# LPmini-Prototype_1_3_bga.net
KiCad netlist of a schematic drawn in EAGLE
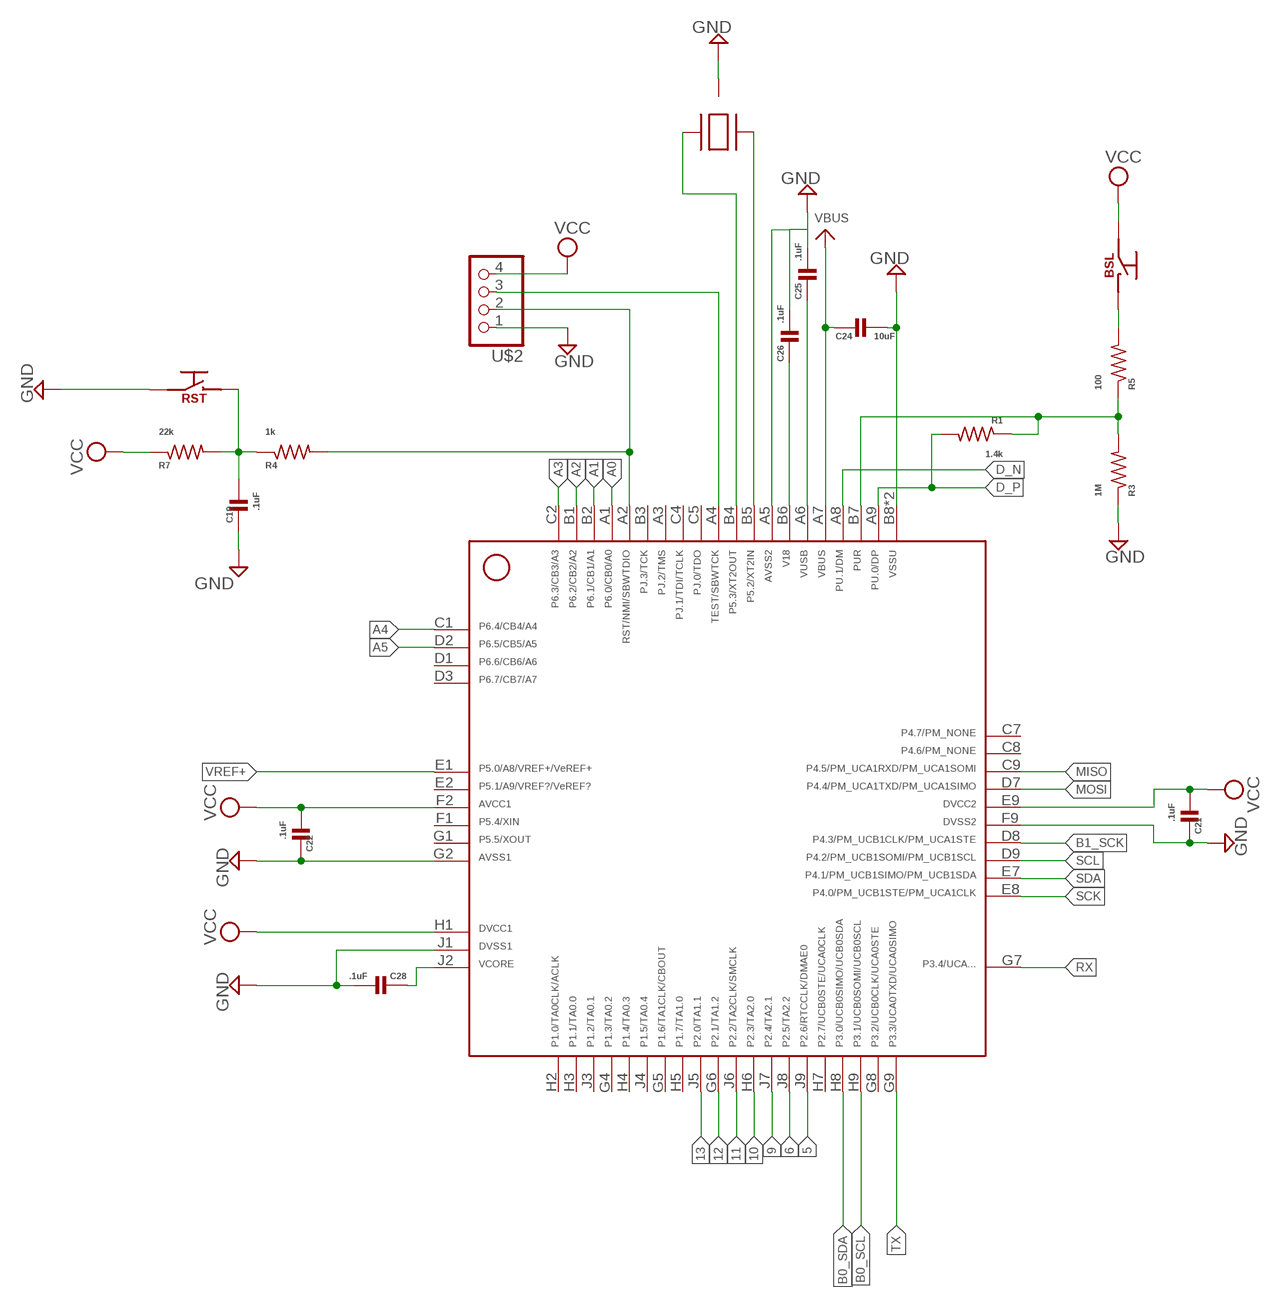
[diagram p0: schematic, sheet 1, part 1 of 2]
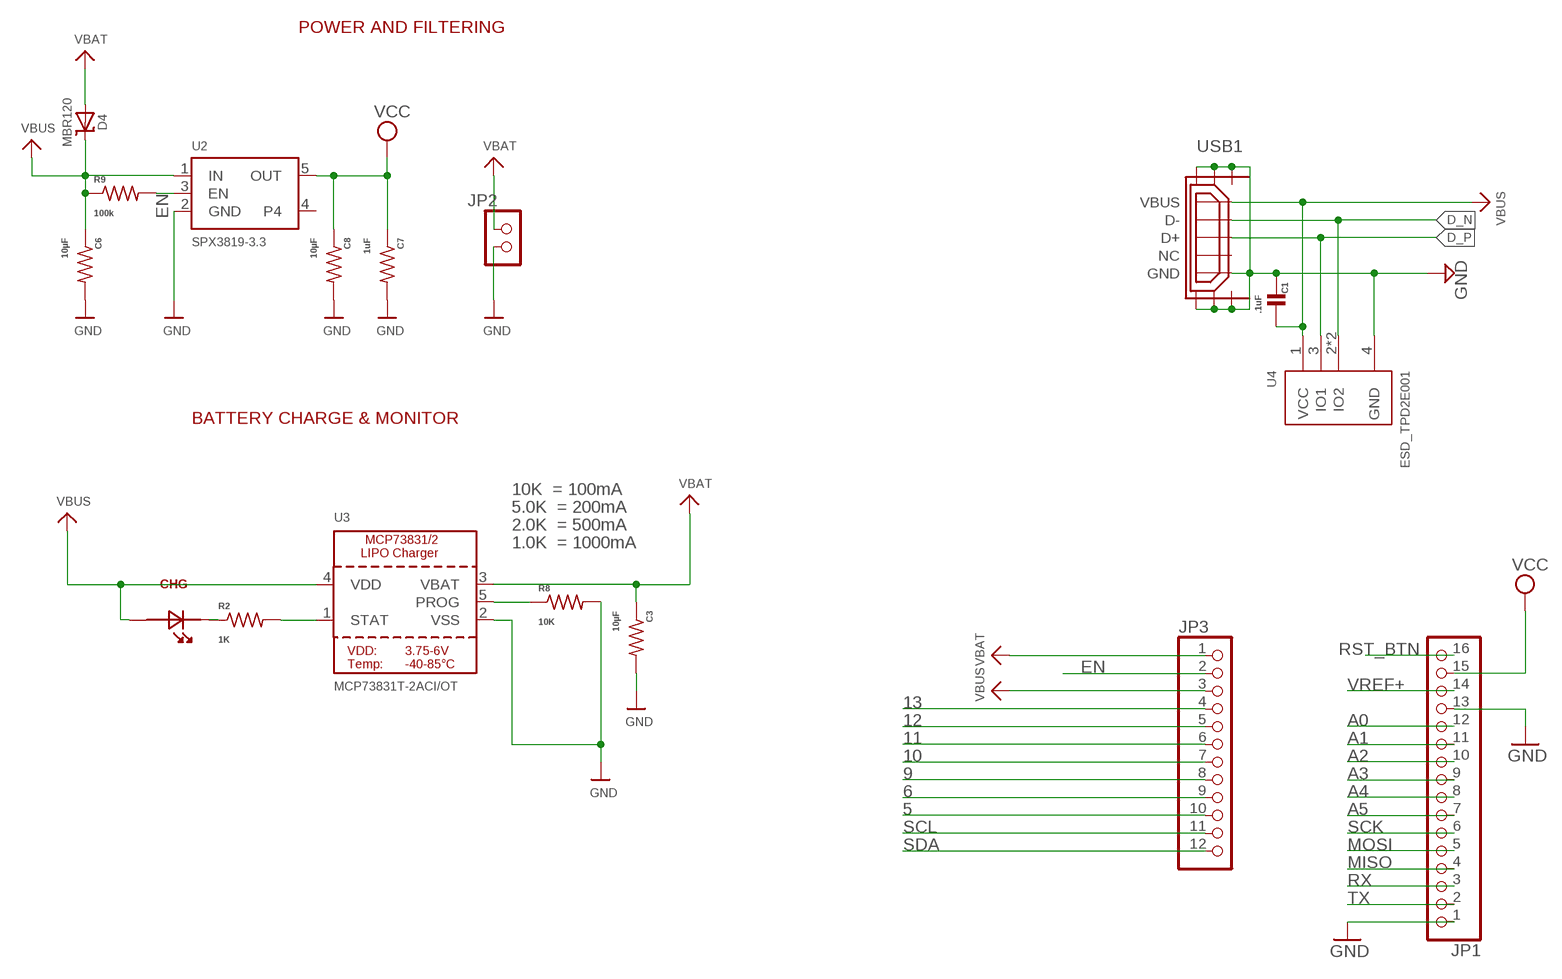
[diagram p1: schematic, sheet 1, part 2 of 2]

(export (version "E")
  (design (tool "Eeschema 10.0.6"))
  (components
    (comp (ref "BSL")
      (value "PB_SMALL_SMD")
      (footprint "eagle-import:PB_KMR2")
      (libsource (lib "eagle-import") (part "PB_SMALL_SMD"))
    )
    (comp (ref "C1")
      (value ".1uF")
      (footprint "eagle-import:C0402")
      (libsource (lib "eagle-import") (part "C-EUC0402"))
    )
    (comp (ref "C3")
      (value "10µF")
      (footprint "eagle-import:R0603")
      (libsource (lib "eagle-import") (part "R-US_R0603"))
    )
    (comp (ref "C6")
      (value "10µF")
      (footprint "eagle-import:R0603")
      (libsource (lib "eagle-import") (part "R-US_R0603"))
    )
    (comp (ref "C7")
      (value "1uF")
      (footprint "eagle-import:R0402")
      (libsource (lib "eagle-import") (part "R-US_R0402"))
    )
    (comp (ref "C8")
      (value "10µF")
      (footprint "eagle-import:R0603")
      (libsource (lib "eagle-import") (part "R-US_R0603"))
    )
    (comp (ref "C19")
      (value ".1uF")
      (footprint "eagle-import:C0402")
      (libsource (lib "eagle-import") (part "C-EUC0402"))
    )
    (comp (ref "C21")
      (value ".1uF")
      (footprint "eagle-import:C0402")
      (libsource (lib "eagle-import") (part "C-EUC0402"))
    )
    (comp (ref "C22")
      (value ".1uF")
      (footprint "eagle-import:C0402")
      (libsource (lib "eagle-import") (part "C-EUC0402"))
    )
    (comp (ref "C24")
      (value "10uF")
      (footprint "eagle-import:C0603")
      (libsource (lib "eagle-import") (part "C-EUC0603"))
    )
    (comp (ref "C25")
      (value ".1uF")
      (footprint "eagle-import:C0402")
      (libsource (lib "eagle-import") (part "C-EUC0402"))
    )
    (comp (ref "C26")
      (value ".1uF")
      (footprint "eagle-import:C0402")
      (libsource (lib "eagle-import") (part "C-EUC0402"))
    )
    (comp (ref "C28")
      (value ".1uF")
      (footprint "eagle-import:C0402")
      (libsource (lib "eagle-import") (part "C-EUC0402"))
    )
    (comp (ref "CHG")
      (value "ORANGE")
      (footprint "eagle-import:LED_0603")
      (libsource (lib "eagle-import") (part "LED0603"))
    )
    (comp (ref "D4")
      (value "MBR120")
      (footprint "eagle-import:SOD-123")
      (libsource (lib "eagle-import") (part "DIODE-SCHOTTKYSOD-123"))
    )
    (comp (ref "JP1")
      (value "HEADER-1X16ROUND")
      (footprint "eagle-import:1X16_ROUND")
      (libsource (lib "eagle-import") (part "HEADER-1X16ROUND"))
    )
    (comp (ref "JP2")
      (value "0_JOSEPH_PINHD-1X2END")
      (footprint "eagle-import:0_JOSEPH_1X02-END")
      (libsource (lib "eagle-import") (part "0_JOSEPH_PINHD-1X2END"))
    )
    (comp (ref "JP3")
      (value "HEADER-1X12")
      (footprint "eagle-import:1X12_ROUND")
      (libsource (lib "eagle-import") (part "HEADER-1X12"))
    )
    (comp (ref "R1")
      (value "1.4k")
      (footprint "eagle-import:R0402")
      (libsource (lib "eagle-import") (part "R-US_R0402"))
    )
    (comp (ref "R2")
      (value "1K")
      (footprint "eagle-import:R0402")
      (libsource (lib "eagle-import") (part "R-US_R0402"))
    )
    (comp (ref "R3")
      (value "1M")
      (footprint "eagle-import:R0402")
      (libsource (lib "eagle-import") (part "R-US_R0402"))
    )
    (comp (ref "R4")
      (value "1k")
      (footprint "eagle-import:R0402")
      (libsource (lib "eagle-import") (part "R-US_R0402"))
    )
    (comp (ref "R5")
      (value "100")
      (footprint "eagle-import:R0402")
      (libsource (lib "eagle-import") (part "R-US_R0402"))
    )
    (comp (ref "R7")
      (value "22k")
      (footprint "eagle-import:R0402")
      (libsource (lib "eagle-import") (part "R-US_R0402"))
    )
    (comp (ref "R8")
      (value "10K")
      (footprint "eagle-import:R0402")
      (libsource (lib "eagle-import") (part "R-US_R0402"))
    )
    (comp (ref "R9")
      (value "100k")
      (footprint "eagle-import:R0402")
      (libsource (lib "eagle-import") (part "R-US_R0402"))
    )
    (comp (ref "RST")
      (value "PB_SMALL_SMD")
      (footprint "eagle-import:PB_KMR2")
      (libsource (lib "eagle-import") (part "PB_SMALL_SMD"))
    )
    (comp (ref "U$2")
      (value "PINHD_1X4MOLEX_4_1MM")
      (footprint "eagle-import:MOLEX_4_1MM")
      (libsource (lib "eagle-import") (part "PINHD_1X4MOLEX_4_1MM"))
    )
    (comp (ref "U$4")
      (value "MSP430F5528")
      (footprint "eagle-import:80_BGA_MICROSTAR")
      (libsource (lib "eagle-import") (part "MSP430F5528"))
    )
    (comp (ref "U$5")
      (value "CRYSTAL_SMD")
      (footprint "eagle-import:SMD_CRYSTAL")
      (libsource (lib "eagle-import") (part "CRYSTAL_SMD"))
    )
    (comp (ref "U2")
      (value "SPX3819-3.3")
      (footprint "eagle-import:SOT23-5")
      (libsource (lib "eagle-import") (part "VREG_SOT23-5"))
    )
    (comp (ref "U3")
      (value "MCP73831T-2ACI/OT")
      (footprint "eagle-import:SOT23-5")
      (libsource (lib "eagle-import") (part "MCP73831/2"))
    )
    (comp (ref "U4")
      (value "ESD_TPD2E001")
      (footprint "eagle-import:PROJECT7264_TPD2E001-DRL")
      (libsource (lib "eagle-import") (part "ESD_TPD2E001"))
    )
    (comp (ref "USB1")
      (value "USB_CON-UPDATE_USB_MICRO_FLIPPED")
      (footprint "eagle-import:USB_CON-UPDATE_HIROSE-ZX62R-B-5P")
      (libsource (lib "eagle-import") (part "USB_CON-UPDATE_USB_MICRO_FLIPPED"))
    )
  )
  (nets
    (net (code "1") (name "/EN") (class "Default")
      (node (ref "JP3") (pin "2") (pinfunction "2_2") (pintype "passive"))
      (node (ref "R9") (pin "2") (pinfunction "2_2") (pintype "passive"))
      (node (ref "U2") (pin "3") (pinfunction "EN_3") (pintype "input"))
    )
    (net (code "2") (name "/RST_BTN") (class "Default")
      (node (ref "C19") (pin "1") (pinfunction "1_1") (pintype "passive"))
      (node (ref "JP1") (pin "16") (pinfunction "16_16") (pintype "passive"))
      (node (ref "R4") (pin "1") (pinfunction "1_1") (pintype "passive"))
      (node (ref "R7") (pin "2") (pinfunction "2_2") (pintype "passive"))
      (node (ref "RST") (pin "2A") (pinfunction "B_2A") (pintype "bidirectional"))
      (node (ref "RST") (pin "2B") (pinfunction "B_2B") (pintype "bidirectional"))
    )
    (net (code "3") (name "5") (class "Default")
      (node (ref "JP3") (pin "10") (pinfunction "10_10") (pintype "passive"))
      (node (ref "U$4") (pin "J9") (pinfunction "J9_J9") (pintype "bidirectional"))
    )
    (net (code "4") (name "6") (class "Default")
      (node (ref "JP3") (pin "9") (pinfunction "9_9") (pintype "passive"))
      (node (ref "U$4") (pin "J8") (pinfunction "J8_J8") (pintype "bidirectional"))
    )
    (net (code "5") (name "9") (class "Default")
      (node (ref "JP3") (pin "8") (pinfunction "8_8") (pintype "passive"))
      (node (ref "U$4") (pin "J7") (pinfunction "J7_J7") (pintype "bidirectional"))
    )
    (net (code "6") (name "10") (class "Default")
      (node (ref "JP3") (pin "7") (pinfunction "7_7") (pintype "passive"))
      (node (ref "U$4") (pin "H6") (pinfunction "H6_H6") (pintype "bidirectional"))
    )
    (net (code "7") (name "11") (class "Default")
      (node (ref "JP3") (pin "6") (pinfunction "6_6") (pintype "passive"))
      (node (ref "U$4") (pin "J6") (pinfunction "J6_J6") (pintype "bidirectional"))
    )
    (net (code "8") (name "12") (class "Default")
      (node (ref "JP3") (pin "5") (pinfunction "5_5") (pintype "passive"))
      (node (ref "U$4") (pin "G6") (pinfunction "G6_G6") (pintype "bidirectional"))
    )
    (net (code "9") (name "13") (class "Default")
      (node (ref "JP3") (pin "4") (pinfunction "4_4") (pintype "passive"))
      (node (ref "U$4") (pin "J5") (pinfunction "J5_J5") (pintype "bidirectional"))
    )
    (net (code "10") (name "A0") (class "Default")
      (node (ref "JP1") (pin "12") (pinfunction "12_12") (pintype "passive"))
      (node (ref "U$4") (pin "A1") (pinfunction "A1_A1") (pintype "bidirectional"))
    )
    (net (code "11") (name "A1") (class "Default")
      (node (ref "JP1") (pin "11") (pinfunction "11_11") (pintype "passive"))
      (node (ref "U$4") (pin "B2") (pinfunction "B2_B2") (pintype "bidirectional"))
    )
    (net (code "12") (name "A2") (class "Default")
      (node (ref "JP1") (pin "10") (pinfunction "10_10") (pintype "passive"))
      (node (ref "U$4") (pin "B1") (pinfunction "B1_B1") (pintype "bidirectional"))
    )
    (net (code "13") (name "A3") (class "Default")
      (node (ref "JP1") (pin "9") (pinfunction "9_9") (pintype "passive"))
      (node (ref "U$4") (pin "C2") (pinfunction "C2_C2") (pintype "bidirectional"))
    )
    (net (code "14") (name "A4") (class "Default")
      (node (ref "JP1") (pin "8") (pinfunction "8_8") (pintype "passive"))
      (node (ref "U$4") (pin "C1") (pinfunction "C1_C1") (pintype "bidirectional"))
    )
    (net (code "15") (name "A5") (class "Default")
      (node (ref "JP1") (pin "7") (pinfunction "7_7") (pintype "passive"))
      (node (ref "U$4") (pin "D2") (pinfunction "D2_D2") (pintype "bidirectional"))
    )
    (net (code "16") (name "B0_SCL") (class "Default")
      (node (ref "U$4") (pin "H9") (pinfunction "H9_H9") (pintype "bidirectional"))
    )
    (net (code "17") (name "B0_SDA") (class "Default")
      (node (ref "U$4") (pin "H8") (pinfunction "H8_H8") (pintype "bidirectional"))
    )
    (net (code "18") (name "B1_SCK") (class "Default")
      (node (ref "U$4") (pin "D8") (pinfunction "D8_D8") (pintype "bidirectional"))
    )
    (net (code "19") (name "D_N") (class "Default")
      (node (ref "U$4") (pin "A8") (pinfunction "A8_A8") (pintype "bidirectional"))
      (node (ref "U4") (pin "2") (pinfunction "IO2_2") (pintype "bidirectional"))
      (node (ref "U4") (pin "5") (pinfunction "IO2_5") (pintype "bidirectional"))
      (node (ref "USB1") (pin "D-") (pinfunction "D-_D-") (pintype "input"))
    )
    (net (code "20") (name "D_P") (class "Default")
      (node (ref "R1") (pin "2") (pinfunction "2_2") (pintype "passive"))
      (node (ref "U$4") (pin "A9") (pinfunction "A9_A9") (pintype "bidirectional"))
      (node (ref "U4") (pin "3") (pinfunction "IO1_3") (pintype "bidirectional"))
      (node (ref "USB1") (pin "D+") (pinfunction "D+_D+") (pintype "input"))
    )
    (net (code "21") (name "GND") (class "Default")
      (node (ref "C1") (pin "2") (pinfunction "2_2") (pintype "passive"))
      (node (ref "C19") (pin "2") (pinfunction "2_2") (pintype "passive"))
      (node (ref "C21") (pin "2") (pinfunction "2_2") (pintype "passive"))
      (node (ref "C22") (pin "2") (pinfunction "2_2") (pintype "passive"))
      (node (ref "C24") (pin "2") (pinfunction "2_2") (pintype "passive"))
      (node (ref "C25") (pin "2") (pinfunction "2_2") (pintype "passive"))
      (node (ref "C26") (pin "2") (pinfunction "2_2") (pintype "passive"))
      (node (ref "C28") (pin "2") (pinfunction "2_2") (pintype "passive"))
      (node (ref "C3") (pin "2") (pinfunction "2_2") (pintype "passive"))
      (node (ref "C6") (pin "2") (pinfunction "2_2") (pintype "passive"))
      (node (ref "C7") (pin "2") (pinfunction "2_2") (pintype "passive"))
      (node (ref "C8") (pin "2") (pinfunction "2_2") (pintype "passive"))
      (node (ref "JP1") (pin "1") (pinfunction "1_1") (pintype "passive"))
      (node (ref "JP1") (pin "13") (pinfunction "13_13") (pintype "passive"))
      (node (ref "JP2") (pin "2") (pinfunction "2_2") (pintype "passive"))
      (node (ref "R3") (pin "1") (pinfunction "1_1") (pintype "passive"))
      (node (ref "R8") (pin "2") (pinfunction "2_2") (pintype "passive"))
      (node (ref "RST") (pin "1A") (pinfunction "A_1A") (pintype "bidirectional"))
      (node (ref "RST") (pin "1B") (pinfunction "A_1B") (pintype "bidirectional"))
      (node (ref "U$2") (pin "1") (pinfunction "1_1") (pintype "passive"))
      (node (ref "U$4") (pin "A5") (pinfunction "A5_A5") (pintype "power_in"))
      (node (ref "U$4") (pin "B8") (pinfunction "B8,B9_B8") (pintype "power_in"))
      (node (ref "U$4") (pin "B9") (pinfunction "B8,B9_B9") (pintype "power_in"))
      (node (ref "U$4") (pin "F9") (pinfunction "F9_F9") (pintype "power_in"))
      (node (ref "U$4") (pin "G2") (pinfunction "G2_G2") (pintype "power_in"))
      (node (ref "U$4") (pin "J1") (pinfunction "J1_J1") (pintype "power_in"))
      (node (ref "U$5") (pin "2") (pinfunction "GND_2") (pintype "bidirectional"))
      (node (ref "U$5") (pin "4") (pinfunction "GND_4") (pintype "bidirectional"))
      (node (ref "U2") (pin "2") (pinfunction "GND_2") (pintype "power_in"))
      (node (ref "U3") (pin "2") (pinfunction "VSS_2") (pintype "power_in"))
      (node (ref "U4") (pin "4") (pinfunction "GND_4") (pintype "power_in"))
      (node (ref "USB1") (pin "GND") (pinfunction "GND_GND") (pintype "input"))
      (node (ref "USB1") (pin "SHIELD1") (pinfunction "SHIELD1_SHIELD1") (pintype "bidirectional"))
      (node (ref "USB1") (pin "SHIELD2") (pinfunction "SHIELD2_SHIELD2") (pintype "bidirectional"))
      (node (ref "USB1") (pin "SHIELD3") (pinfunction "SHIELD3_SHIELD3") (pintype "bidirectional"))
      (node (ref "USB1") (pin "SHIELD4") (pinfunction "SHIELD4_SHIELD4") (pintype "bidirectional"))
      (node (ref "USB1") (pin "SHIELD5") (pinfunction "SHIELD5_SHIELD5") (pintype "bidirectional"))
      (node (ref "USB1") (pin "SHIELD6") (pinfunction "SHIELD6_SHIELD6") (pintype "bidirectional"))
    )
    (net (code "22") (name "MISO") (class "Default")
      (node (ref "JP1") (pin "4") (pinfunction "4_4") (pintype "passive"))
      (node (ref "U$4") (pin "C9") (pinfunction "C9_C9") (pintype "bidirectional"))
    )
    (net (code "23") (name "MOSI") (class "Default")
      (node (ref "JP1") (pin "5") (pinfunction "5_5") (pintype "passive"))
      (node (ref "U$4") (pin "D7") (pinfunction "D7_D7") (pintype "bidirectional"))
    )
    (net (code "24") (name "Net-(BSL-B-Pad2A)") (class "Default")
      (node (ref "BSL") (pin "2A") (pinfunction "B_2A") (pintype "bidirectional"))
      (node (ref "BSL") (pin "2B") (pinfunction "B_2B") (pintype "bidirectional"))
      (node (ref "R5") (pin "2") (pinfunction "2_2") (pintype "passive"))
    )
    (net (code "25") (name "Net-(C25-Pad1)") (class "Default")
      (node (ref "C25") (pin "1") (pinfunction "1_1") (pintype "passive"))
      (node (ref "U$4") (pin "A6") (pinfunction "A6_A6") (pintype "power_in"))
    )
    (net (code "26") (name "Net-(C26-Pad1)") (class "Default")
      (node (ref "C26") (pin "1") (pinfunction "1_1") (pintype "passive"))
      (node (ref "U$4") (pin "B6") (pinfunction "B6_B6") (pintype "power_in"))
    )
    (net (code "27") (name "Net-(C28-Pad1)") (class "Default")
      (node (ref "C28") (pin "1") (pinfunction "1_1") (pintype "passive"))
      (node (ref "U$4") (pin "J2") (pinfunction "J2_J2") (pintype "power_in"))
    )
    (net (code "28") (name "Net-(CHG-C)") (class "Default")
      (node (ref "CHG") (pin "K") (pinfunction "C_K") (pintype "bidirectional"))
      (node (ref "R2") (pin "1") (pinfunction "1_1") (pintype "passive"))
    )
    (net (code "29") (name "Net-(R1-Pad1)") (class "Default")
      (node (ref "R1") (pin "1") (pinfunction "1_1") (pintype "passive"))
      (node (ref "R3") (pin "2") (pinfunction "2_2") (pintype "passive"))
      (node (ref "R5") (pin "1") (pinfunction "1_1") (pintype "passive"))
      (node (ref "U$4") (pin "B7") (pinfunction "B7_B7") (pintype "bidirectional"))
    )
    (net (code "30") (name "Net-(R4-Pad2)") (class "Default")
      (node (ref "R4") (pin "2") (pinfunction "2_2") (pintype "passive"))
      (node (ref "U$2") (pin "2") (pinfunction "2_2") (pintype "passive"))
      (node (ref "U$4") (pin "A2") (pinfunction "A2_A2") (pintype "bidirectional"))
    )
    (net (code "31") (name "Net-(U$2-Pad3)") (class "Default")
      (node (ref "U$2") (pin "3") (pinfunction "3_3") (pintype "passive"))
      (node (ref "U$4") (pin "A4") (pinfunction "A4_A4") (pintype "input"))
    )
    (net (code "32") (name "Net-(U$5-P$1)") (class "Default")
      (node (ref "U$4") (pin "B5") (pinfunction "B5_B5") (pintype "bidirectional"))
      (node (ref "U$5") (pin "1") (pinfunction "P$1_1") (pintype "bidirectional"))
    )
    (net (code "33") (name "Net-(U$5-P$2)") (class "Default")
      (node (ref "U$4") (pin "B4") (pinfunction "B4_B4") (pintype "bidirectional"))
      (node (ref "U$5") (pin "3") (pinfunction "P$2_3") (pintype "bidirectional"))
    )
    (net (code "34") (name "Net-(U3-PROG)") (class "Default")
      (node (ref "R8") (pin "1") (pinfunction "1_1") (pintype "passive"))
      (node (ref "U3") (pin "5") (pinfunction "PROG_5") (pintype "input"))
    )
    (net (code "35") (name "Net-(U3-STAT)") (class "Default")
      (node (ref "R2") (pin "2") (pinfunction "2_2") (pintype "passive"))
      (node (ref "U3") (pin "1") (pinfunction "STAT_1") (pintype "output"))
    )
    (net (code "36") (name "RX") (class "Default")
      (node (ref "JP1") (pin "3") (pinfunction "3_3") (pintype "passive"))
      (node (ref "U$4") (pin "G7") (pinfunction "G7_G7") (pintype "bidirectional"))
    )
    (net (code "37") (name "SCK") (class "Default")
      (node (ref "JP1") (pin "6") (pinfunction "6_6") (pintype "passive"))
      (node (ref "U$4") (pin "E8") (pinfunction "E8_E8") (pintype "bidirectional"))
    )
    (net (code "38") (name "SCL") (class "Default")
      (node (ref "JP3") (pin "11") (pinfunction "11_11") (pintype "passive"))
      (node (ref "U$4") (pin "D9") (pinfunction "D9_D9") (pintype "bidirectional"))
    )
    (net (code "39") (name "SDA") (class "Default")
      (node (ref "JP3") (pin "12") (pinfunction "12_12") (pintype "passive"))
      (node (ref "U$4") (pin "E7") (pinfunction "E7_E7") (pintype "bidirectional"))
    )
    (net (code "40") (name "TX") (class "Default")
      (node (ref "JP1") (pin "2") (pinfunction "2_2") (pintype "passive"))
      (node (ref "U$4") (pin "G9") (pinfunction "G9_G9") (pintype "bidirectional"))
    )
    (net (code "41") (name "VBAT") (class "Default")
      (node (ref "C3") (pin "1") (pinfunction "1_1") (pintype "passive"))
      (node (ref "D4") (pin "A") (pinfunction "A_A") (pintype "passive"))
      (node (ref "JP2") (pin "1") (pinfunction "1_1") (pintype "passive"))
      (node (ref "JP3") (pin "1") (pinfunction "1_1") (pintype "passive"))
      (node (ref "U3") (pin "3") (pinfunction "VBAT_3") (pintype "power_in"))
    )
    (net (code "42") (name "VBUS") (class "Default")
      (node (ref "C1") (pin "1") (pinfunction "1_1") (pintype "passive"))
      (node (ref "C24") (pin "1") (pinfunction "1_1") (pintype "passive"))
      (node (ref "C6") (pin "1") (pinfunction "1_1") (pintype "passive"))
      (node (ref "CHG") (pin "A") (pinfunction "A_A") (pintype "bidirectional"))
      (node (ref "D4") (pin "C") (pinfunction "C_C") (pintype "passive"))
      (node (ref "JP3") (pin "3") (pinfunction "3_3") (pintype "passive"))
      (node (ref "R9") (pin "1") (pinfunction "1_1") (pintype "passive"))
      (node (ref "U$4") (pin "A7") (pinfunction "A7_A7") (pintype "power_in"))
      (node (ref "U2") (pin "1") (pinfunction "IN_1") (pintype "power_in"))
      (node (ref "U3") (pin "4") (pinfunction "VDD_4") (pintype "power_in"))
      (node (ref "U4") (pin "1") (pinfunction "VCC_1") (pintype "power_in"))
      (node (ref "USB1") (pin "VBUS") (pinfunction "VBUS_VBUS") (pintype "input"))
    )
    (net (code "43") (name "VCC") (class "Default")
      (node (ref "BSL") (pin "1A") (pinfunction "A_1A") (pintype "bidirectional"))
      (node (ref "BSL") (pin "1B") (pinfunction "A_1B") (pintype "bidirectional"))
      (node (ref "C21") (pin "1") (pinfunction "1_1") (pintype "passive"))
      (node (ref "C22") (pin "1") (pinfunction "1_1") (pintype "passive"))
      (node (ref "C7") (pin "1") (pinfunction "1_1") (pintype "passive"))
      (node (ref "C8") (pin "1") (pinfunction "1_1") (pintype "passive"))
      (node (ref "JP1") (pin "15") (pinfunction "15_15") (pintype "passive"))
      (node (ref "R7") (pin "1") (pinfunction "1_1") (pintype "passive"))
      (node (ref "U$2") (pin "4") (pinfunction "4_4") (pintype "passive"))
      (node (ref "U$4") (pin "E9") (pinfunction "E9_E9") (pintype "power_in"))
      (node (ref "U$4") (pin "F2") (pinfunction "F2_F2") (pintype "power_in"))
      (node (ref "U$4") (pin "H1") (pinfunction "H1_H1") (pintype "power_in"))
      (node (ref "U2") (pin "5") (pinfunction "OUT_5") (pintype "power_in"))
    )
    (net (code "44") (name "VREF+") (class "Default")
      (node (ref "JP1") (pin "14") (pinfunction "14_14") (pintype "passive"))
      (node (ref "U$4") (pin "E1") (pinfunction "E1_E1") (pintype "bidirectional"))
    )
    (net (code "45") (name "unconnected-(U$4-PadA3)") (class "Default")
      (node (ref "U$4") (pin "A3") (pinfunction "A3_A3") (pintype "bidirectional"))
    )
    (net (code "46") (name "unconnected-(U$4-PadB3)") (class "Default")
      (node (ref "U$4") (pin "B3") (pinfunction "B3_B3") (pintype "bidirectional"))
    )
    (net (code "47") (name "unconnected-(U$4-PadC4)") (class "Default")
      (node (ref "U$4") (pin "C4") (pinfunction "C4_C4") (pintype "bidirectional"))
    )
    (net (code "48") (name "unconnected-(U$4-PadC5)") (class "Default")
      (node (ref "U$4") (pin "C5") (pinfunction "C5_C5") (pintype "bidirectional"))
    )
    (net (code "49") (name "unconnected-(U$4-PadC7)") (class "Default")
      (node (ref "U$4") (pin "C7") (pinfunction "C7_C7") (pintype "bidirectional"))
    )
    (net (code "50") (name "unconnected-(U$4-PadC8)") (class "Default")
      (node (ref "U$4") (pin "C8") (pinfunction "C8_C8") (pintype "bidirectional"))
    )
    (net (code "51") (name "unconnected-(U$4-PadD1)") (class "Default")
      (node (ref "U$4") (pin "D1") (pinfunction "D1_D1") (pintype "bidirectional"))
    )
    (net (code "52") (name "unconnected-(U$4-PadD3)") (class "Default")
      (node (ref "U$4") (pin "D3") (pinfunction "D3_D3") (pintype "bidirectional"))
    )
    (net (code "53") (name "unconnected-(U$4-PadE2)") (class "Default")
      (node (ref "U$4") (pin "E2") (pinfunction "E2_E2") (pintype "bidirectional"))
    )
    (net (code "54") (name "unconnected-(U$4-PadF1)") (class "Default")
      (node (ref "U$4") (pin "F1") (pinfunction "F1_F1") (pintype "bidirectional"))
    )
    (net (code "55") (name "unconnected-(U$4-PadG1)") (class "Default")
      (node (ref "U$4") (pin "G1") (pinfunction "G1_G1") (pintype "bidirectional"))
    )
    (net (code "56") (name "unconnected-(U$4-PadG4)") (class "Default")
      (node (ref "U$4") (pin "G4") (pinfunction "G4_G4") (pintype "bidirectional"))
    )
    (net (code "57") (name "unconnected-(U$4-PadG5)") (class "Default")
      (node (ref "U$4") (pin "G5") (pinfunction "G5_G5") (pintype "bidirectional"))
    )
    (net (code "58") (name "unconnected-(U$4-PadG8)") (class "Default")
      (node (ref "U$4") (pin "G8") (pinfunction "G8_G8") (pintype "bidirectional"))
    )
    (net (code "59") (name "unconnected-(U$4-PadH2)") (class "Default")
      (node (ref "U$4") (pin "H2") (pinfunction "H2_H2") (pintype "bidirectional"))
    )
    (net (code "60") (name "unconnected-(U$4-PadH3)") (class "Default")
      (node (ref "U$4") (pin "H3") (pinfunction "H3_H3") (pintype "bidirectional"))
    )
    (net (code "61") (name "unconnected-(U$4-PadH4)") (class "Default")
      (node (ref "U$4") (pin "H4") (pinfunction "H4_H4") (pintype "bidirectional"))
    )
    (net (code "62") (name "unconnected-(U$4-PadH5)") (class "Default")
      (node (ref "U$4") (pin "H5") (pinfunction "H5_H5") (pintype "bidirectional"))
    )
    (net (code "63") (name "unconnected-(U$4-PadH7)") (class "Default")
      (node (ref "U$4") (pin "H7") (pinfunction "H7_H7") (pintype "bidirectional"))
    )
    (net (code "64") (name "unconnected-(U$4-PadJ3)") (class "Default")
      (node (ref "U$4") (pin "J3") (pinfunction "J3_J3") (pintype "bidirectional"))
    )
    (net (code "65") (name "unconnected-(U$4-PadJ4)") (class "Default")
      (node (ref "U$4") (pin "J4") (pinfunction "J4_J4") (pintype "bidirectional"))
    )
    (net (code "66") (name "unconnected-(U2-P4-Pad4)") (class "Default")
      (node (ref "U2") (pin "4") (pinfunction "P4_4") (pintype "bidirectional"))
    )
    (net (code "67") (name "unconnected-(USB1-PadNC)") (class "Default")
      (node (ref "USB1") (pin "NC") (pinfunction "NC_NC") (pintype "input"))
    )
  )
)
